# Buck.net
KiCad netlist of a schematic drawn in Altium Designer
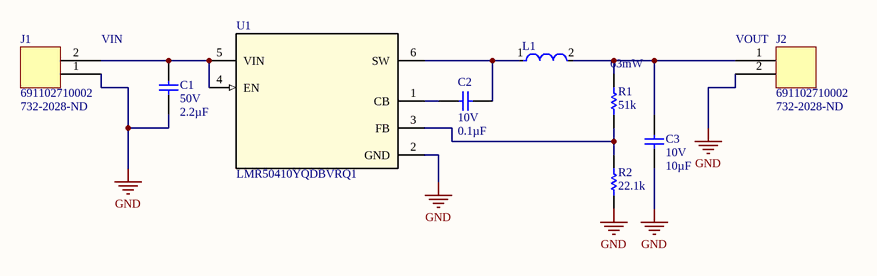
[diagram p0: Buck.SchDoc]

(export (version "E")
  (design (tool "Eeschema 10.0.6"))
  (components
    (comp (ref "C1")
      (value "2.2µF")
      (footprint "CAP1210R")
      (description "CAP CER 2.2UF 50V X7R 1210")
      (fields
        (field (name "VOLTAGE - RATED") "50V")
        (field (name "TOLERANCE") "±20%")
        (field (name "MANUFACTURER") "TDK Corporation")
      )
      (libsource (lib "University of Toronto Aerospace Team") (part "Cap-2"))
    )
    (comp (ref "C2")
      (value "0.1µF")
      (footprint "CAP0603R")
      (description "CAP CER 10UF 10V X5R 0603")
      (fields
        (field (name "VOLTAGE - RATED") "10V")
        (field (name "MANUFACTURER") "Taiyo Yuden")
        (field (name "TOLERANCE") "±20%")
      )
      (libsource (lib "University of Toronto Aerospace Team") (part "Cap-2"))
    )
    (comp (ref "C3")
      (value "10µF")
      (footprint "CAP0805R")
      (description "CAP CER 10UF 10V X7R 0805")
      (fields
        (field (name "VOLTAGE - RATED") "10V")
        (field (name "TOLERANCE") "±10%")
        (field (name "MANUFACTURER") "Murata Electronics")
      )
      (libsource (lib "University of Toronto Aerospace Team") (part "Cap-2"))
    )
    (comp (ref "J1")
      (value "691102710002")
      (footprint "CON2_SCREW_5.00MM_691102710002")
      (description "2 Position Wire to Board Terminal Block Horizontal with Board 0.197\" (5.00mm) Through Hole")
      (fields
        (field (name "SUPPLIER PART NUMBER 1") "732-2028-ND")
        (field (name "MANUFACTURER") "Würth Elektronik")
      )
      (libsource (lib "University of Toronto Aerospace Team") (part "691102710002"))
    )
    (comp (ref "J2")
      (value "691102710002")
      (footprint "CON2_SCREW_5.00MM_691102710002")
      (description "2 Position Wire to Board Terminal Block Horizontal with Board 0.197\" (5.00mm) Through Hole")
      (fields
        (field (name "SUPPLIER PART NUMBER 1") "732-2028-ND")
        (field (name "MANUFACTURER") "Würth Elektronik")
      )
      (libsource (lib "") (part "691102710002_1"))
    )
    (comp (ref "L1")
      (value "DFE322520FD-3R3M=P2")
      (footprint "FP-DFE322520F_D-IPC_B")
      (description "FIXED IND 3.3UH 2.3A 65 MOHM SMD")
      (libsource (lib "University of Toronto Aerospace Team") (part "725321dda6339637d4d059423bc1c3c"))
    )
    (comp (ref "R1")
      (value "51k")
      (footprint "RES0603R")
      (description "Chip Resistor, 51 KOhm, +/- 5%, 0.063 W, -55 to 155 degC, 0402 (1005 Metric)")
      (fields
        (field (name "MANUFACTURER") "Vishay Dale")
        (field (name "TOLERANCE") "±1%")
        (field (name "POWER") "63mW")
      )
      (libsource (lib "University of Toronto Aerospace Team") (part "Res-2"))
    )
    (comp (ref "R2")
      (value "22.1k")
      (footprint "RES0603R")
      (description "RES SMD 22.1K OHM 1% 1/10W 0603")
      (fields (field (name "MANUFACTURER") "Vishay Dale") (field (name "TOLERANCE") "±1%"))
      (libsource (lib "University of Toronto Aerospace Team") (part "Res-2"))
    )
    (comp (ref "U1")
      (value "LMR50410YQDBVRQ1")
      (footprint "DBV0006A-IPC_A")
      (description "No Description Available")
      (libsource (lib "LMR50410YQDBVRQ1") (part "LMR50410YQDBVRQ1"))
    )
  )
  (nets
    (net (code "1") (name "GND") (class "Default")
      (node (ref "C1") (pin "1") (pinfunction "1_1") (pintype "passive"))
      (node (ref "C3") (pin "1") (pinfunction "1_1") (pintype "passive"))
      (node (ref "J1") (pin "1") (pinfunction "1_1") (pintype "passive"))
      (node (ref "J2") (pin "2") (pinfunction "2_2") (pintype "passive"))
      (node (ref "R2") (pin "1") (pinfunction "1_1") (pintype "passive"))
      (node (ref "U1") (pin "2") (pinfunction "GND_2") (pintype "power_in"))
    )
    (net (code "2") (name "Net-(C3-Pad2)") (class "Default")
      (node (ref "C3") (pin "2") (pinfunction "2_2") (pintype "passive"))
      (node (ref "J2") (pin "1") (pinfunction "1_1") (pintype "passive"))
      (node (ref "L1") (pin "2") (pinfunction "2_2") (pintype "passive"))
      (node (ref "R1") (pin "2") (pinfunction "2_2") (pintype "passive"))
    )
    (net (code "3") (name "Net-(U1-CB)") (class "Default")
      (node (ref "C2") (pin "2") (pinfunction "2_2") (pintype "passive"))
      (node (ref "U1") (pin "1") (pinfunction "CB_1") (pintype "passive"))
    )
    (net (code "4") (name "Net-(U1-EN)") (class "Default")
      (node (ref "C1") (pin "2") (pinfunction "2_2") (pintype "passive"))
      (node (ref "J1") (pin "2") (pinfunction "2_2") (pintype "passive"))
      (node (ref "U1") (pin "4") (pinfunction "EN_4") (pintype "input"))
      (node (ref "U1") (pin "5") (pinfunction "VIN_5") (pintype "power_in"))
    )
    (net (code "5") (name "Net-(U1-FB)") (class "Default")
      (node (ref "R1") (pin "1") (pinfunction "1_1") (pintype "passive"))
      (node (ref "R2") (pin "2") (pinfunction "2_2") (pintype "passive"))
      (node (ref "U1") (pin "3") (pinfunction "FB_3") (pintype "passive"))
    )
    (net (code "6") (name "Net-(U1-SW)") (class "Default")
      (node (ref "C2") (pin "1") (pinfunction "1_1") (pintype "passive"))
      (node (ref "L1") (pin "1") (pinfunction "1_1") (pintype "passive"))
      (node (ref "U1") (pin "6") (pinfunction "SW_6") (pintype "power_in"))
    )
  )
)
